# 08_-_RTD.net
KiCad netlist of a schematic drawn in Altium Designer
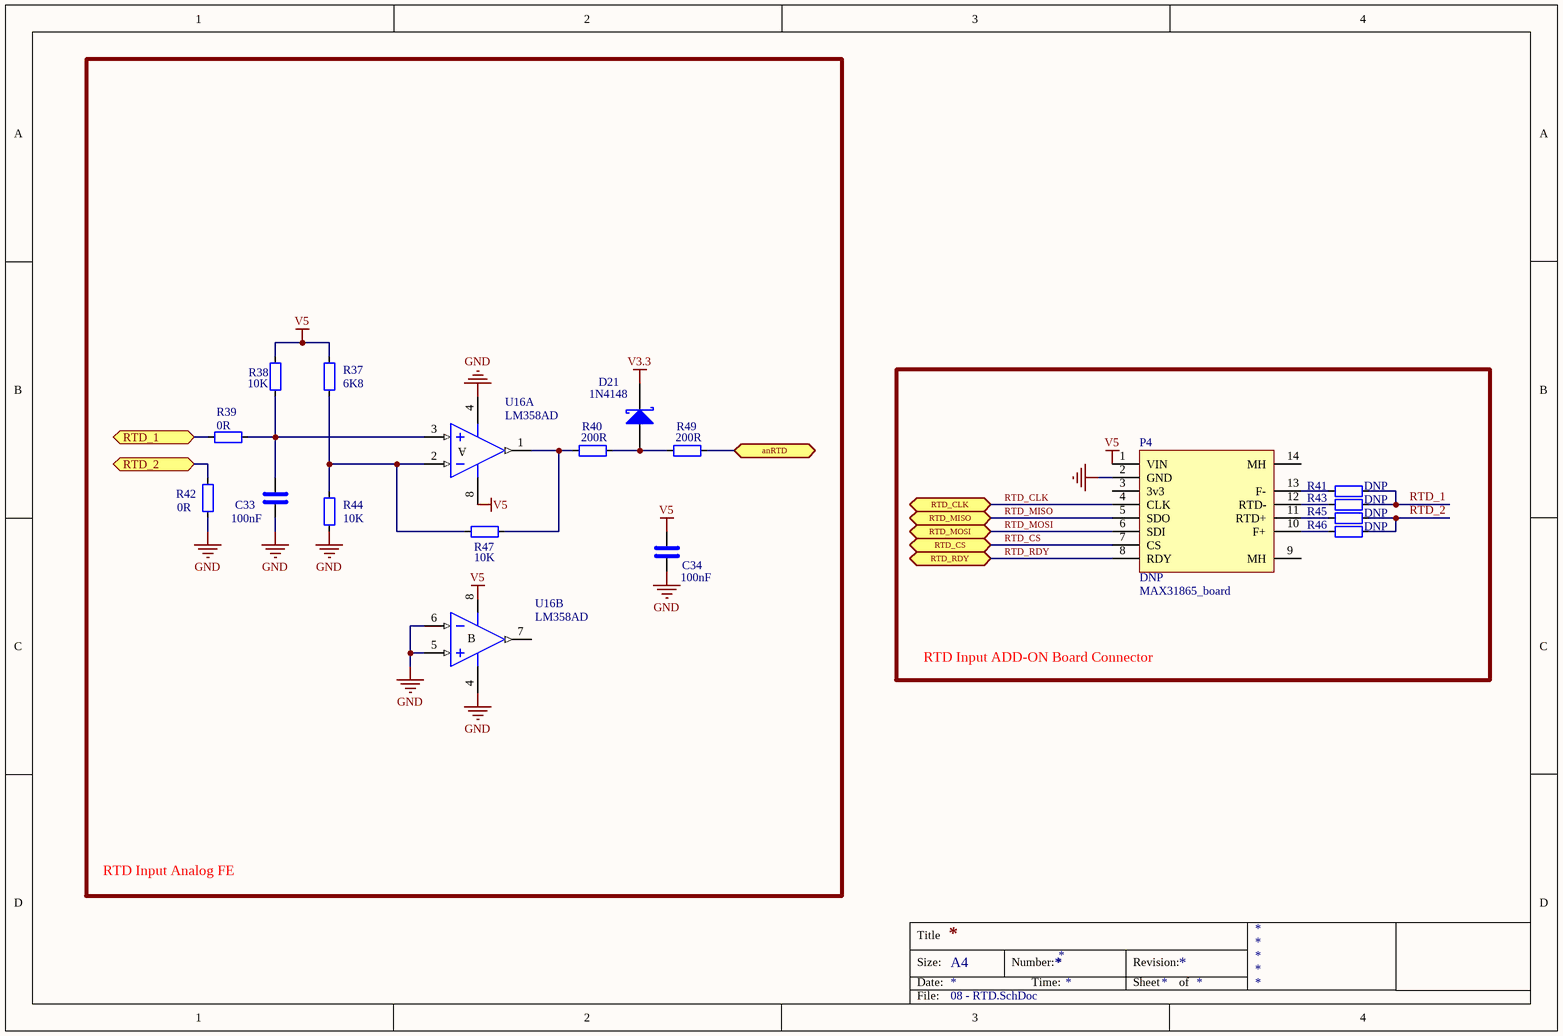
[diagram p0: 08 - RTD.SchDoc]

(export (version "E")
  (design (tool "Eeschema 10.0.6"))
  (components
    (comp (ref "C33")
      (value "100nF")
      (footprint "CAP_0603")
      (fields (field (name "LCSC PART") "C6119867"))
      (libsource (lib "WalterFeels") (part "C"))
    )
    (comp (ref "C34")
      (value "100nF")
      (footprint "CAP_0603")
      (fields (field (name "LCSC PART") "C6119867"))
      (libsource (lib "WalterFeels") (part "C"))
    )
    (comp (ref "D21")
      (value "1N4148")
      (footprint "SOD323_STM_NW")
      (description "1N4148_KA")
      (fields (field (name "LCSC PART") "C84063"))
      (libsource (lib "ahmet") (part "1N4148_KA"))
    )
    (comp (ref "P4")
      (value "DNP")
      (footprint "MAX31865_board")
      (description "MAX31865_board")
      (fields (field (name "ALTIUM_VALUE") "MAX31865_board") (field (name "PUBLISHER") "Altium Limited"))
      (libsource (lib "ahmet") (part "MAX31865_board"))
    )
    (comp (ref "R37")
      (value "6K8")
      (footprint "RES_0603")
      (fields (field (name "Comment") "60.4Ω"))
      (libsource (lib "") (part "R_1"))
    )
    (comp (ref "R38")
      (value "10K")
      (footprint "RES_0603")
      (fields (field (name "LCSC PART") "C25804") (field (name "Comment") "10K 1%"))
      (libsource (lib "Device") (part "R"))
    )
    (comp (ref "R39")
      (value "0R")
      (footprint "RES_0603")
      (fields (field (name "LCSC PART") "C15402"))
      (libsource (lib "") (part "R_2"))
    )
    (comp (ref "R40")
      (value "200R")
      (footprint "RES_0603")
      (fields (field (name "LCSC PART") "C2907123") (field (name "Comment") "200R %5"))
      (libsource (lib "") (part "R_2"))
    )
    (comp (ref "R41") (value "DNP") (footprint "RES_0603") (libsource (lib "") (part "R_3")))
    (comp (ref "R42")
      (value "0R")
      (footprint "RES_0603")
      (fields (field (name "LCSC PART") "C15402"))
      (libsource (lib "") (part "R_1"))
    )
    (comp (ref "R43") (value "DNP") (footprint "RES_0603") (libsource (lib "") (part "R_3")))
    (comp (ref "R44")
      (value "10K")
      (footprint "RES_0603")
      (fields (field (name "LCSC PART") "C25804") (field (name "Comment") "10K 1%"))
      (libsource (lib "Device") (part "R"))
    )
    (comp (ref "R45") (value "DNP") (footprint "RES_0603") (libsource (lib "") (part "R_3")))
    (comp (ref "R46") (value "DNP") (footprint "RES_0603") (libsource (lib "") (part "R_3")))
    (comp (ref "R47")
      (value "10K")
      (footprint "RES_0603")
      (fields (field (name "LCSC PART") "C25804") (field (name "Comment") "10K 1%"))
      (libsource (lib "") (part "R_3"))
    )
    (comp (ref "R49")
      (value "200R")
      (footprint "RES_0603")
      (fields (field (name "LCSC PART") "C2907123") (field (name "Comment") "200R %5"))
      (libsource (lib "") (part "R_2"))
    )
    (comp (ref "U16")
      (value "LM358AD")
      (footprint "SO8_M")
      (description "Low-Power Dual Operational Amplifier")
      (fields (field (name "LCSC PART") "C5423") (field (name "PUBLISHER") "Altium Limited"))
      (libsource (lib "ST Operational Amplifier") (part "LM358AD"))
    )
  )
  (nets
    (net (code "1") (name "/RTD_1") (class "Default")
      (node (ref "R39") (pin "1") (pinfunction "1_1") (pintype "passive"))
      (node (ref "R41") (pin "1") (pinfunction "1_1") (pintype "passive"))
      (node (ref "R43") (pin "1") (pinfunction "1_1") (pintype "passive"))
    )
    (net (code "2") (name "/RTD_2") (class "Default")
      (node (ref "R42") (pin "1") (pinfunction "1_1") (pintype "passive"))
      (node (ref "R45") (pin "1") (pinfunction "1_1") (pintype "passive"))
      (node (ref "R46") (pin "1") (pinfunction "1_1") (pintype "passive"))
    )
    (net (code "3") (name "/RTD_CLK") (class "Default")
      (node (ref "P4") (pin "4") (pinfunction "CLK_4") (pintype "passive"))
    )
    (net (code "4") (name "/RTD_CS") (class "Default")
      (node (ref "P4") (pin "7") (pinfunction "CS_7") (pintype "passive"))
    )
    (net (code "5") (name "/RTD_MISO") (class "Default")
      (node (ref "P4") (pin "5") (pinfunction "SDO_5") (pintype "passive"))
    )
    (net (code "6") (name "/RTD_MOSI") (class "Default")
      (node (ref "P4") (pin "6") (pinfunction "SDI_6") (pintype "passive"))
    )
    (net (code "7") (name "/RTD_RDY") (class "Default")
      (node (ref "P4") (pin "8") (pinfunction "RDY_8") (pintype "passive"))
    )
    (net (code "8") (name "/anRTD") (class "Default")
      (node (ref "R49") (pin "2") (pinfunction "2_2") (pintype "passive"))
    )
    (net (code "9") (name "GND") (class "Default")
      (node (ref "C33") (pin "2") (pinfunction "2_2") (pintype "passive"))
      (node (ref "C34") (pin "2") (pinfunction "2_2") (pintype "passive"))
      (node (ref "P4") (pin "2") (pinfunction "GND_2") (pintype "passive"))
      (node (ref "R42") (pin "2") (pinfunction "2_2") (pintype "passive"))
      (node (ref "R44") (pin "1") (pinfunction "1_1") (pintype "passive"))
      (node (ref "U16") (pin "4") (pinfunction "V-_4") (pintype "power_in"))
      (node (ref "U16") (pin "5") (pinfunction "IN+_5") (pintype "input"))
      (node (ref "U16") (pin "6") (pinfunction "IN-_6") (pintype "input"))
    )
    (net (code "10") (name "Net-(D21-A)") (class "Default")
      (node (ref "D21") (pin "2") (pinfunction "A_2") (pintype "passive"))
      (node (ref "R40") (pin "2") (pinfunction "2_2") (pintype "passive"))
      (node (ref "R49") (pin "1") (pinfunction "1_1") (pintype "passive"))
    )
    (net (code "11") (name "Net-(P4-F+)") (class "Default")
      (node (ref "P4") (pin "10") (pinfunction "F+_10") (pintype "passive"))
      (node (ref "R46") (pin "2") (pinfunction "2_2") (pintype "passive"))
    )
    (net (code "12") (name "Net-(P4-F-)") (class "Default")
      (node (ref "P4") (pin "13") (pinfunction "F-_13") (pintype "passive"))
      (node (ref "R41") (pin "2") (pinfunction "2_2") (pintype "passive"))
    )
    (net (code "13") (name "Net-(P4-RTD+)") (class "Default")
      (node (ref "P4") (pin "11") (pinfunction "RTD+_11") (pintype "passive"))
      (node (ref "R45") (pin "2") (pinfunction "2_2") (pintype "passive"))
    )
    (net (code "14") (name "Net-(P4-RTD-)") (class "Default")
      (node (ref "P4") (pin "12") (pinfunction "RTD-_12") (pintype "passive"))
      (node (ref "R43") (pin "2") (pinfunction "2_2") (pintype "passive"))
    )
    (net (code "15") (name "Net-(U16A-IN+)") (class "Default")
      (node (ref "C33") (pin "1") (pinfunction "1_1") (pintype "passive"))
      (node (ref "R38") (pin "1") (pinfunction "1_1") (pintype "passive"))
      (node (ref "R39") (pin "2") (pinfunction "2_2") (pintype "passive"))
      (node (ref "U16") (pin "3") (pinfunction "IN+_3") (pintype "input"))
    )
    (net (code "16") (name "Net-(U16A-IN-)") (class "Default")
      (node (ref "R37") (pin "2") (pinfunction "2_2") (pintype "passive"))
      (node (ref "R44") (pin "2") (pinfunction "2_2") (pintype "passive"))
      (node (ref "R47") (pin "2") (pinfunction "2_2") (pintype "passive"))
      (node (ref "U16") (pin "2") (pinfunction "IN-_2") (pintype "input"))
    )
    (net (code "17") (name "Net-(U16A-OUT)") (class "Default")
      (node (ref "R40") (pin "1") (pinfunction "1_1") (pintype "passive"))
      (node (ref "R47") (pin "1") (pinfunction "1_1") (pintype "passive"))
      (node (ref "U16") (pin "1") (pinfunction "OUT_1") (pintype "output"))
    )
    (net (code "18") (name "V3.3") (class "Default")
      (node (ref "D21") (pin "1") (pinfunction "K_1") (pintype "passive"))
    )
    (net (code "19") (name "V5") (class "Default")
      (node (ref "C34") (pin "1") (pinfunction "1_1") (pintype "passive"))
      (node (ref "P4") (pin "1") (pinfunction "VIN_1") (pintype "passive"))
      (node (ref "R37") (pin "1") (pinfunction "1_1") (pintype "passive"))
      (node (ref "R38") (pin "2") (pinfunction "2_2") (pintype "passive"))
      (node (ref "U16") (pin "8") (pinfunction "V+_8") (pintype "power_in"))
    )
    (net (code "20") (name "unconnected-(P4-3v3-Pad3)") (class "Default")
      (node (ref "P4") (pin "3") (pinfunction "3v3_3") (pintype "passive"))
    )
    (net (code "21") (name "unconnected-(P4-MH-Pad9)") (class "Default")
      (node (ref "P4") (pin "9") (pinfunction "MH_9") (pintype "passive"))
    )
    (net (code "22") (name "unconnected-(P4-MH-Pad14)") (class "Default")
      (node (ref "P4") (pin "14") (pinfunction "MH_14") (pintype "passive"))
    )
    (net (code "23") (name "unconnected-(U16B-OUT-Pad7)") (class "Default")
      (node (ref "U16") (pin "7") (pinfunction "OUT_7") (pintype "output"))
    )
    (net (code "24") (name "unconnected-(U16B-V+-Pad8)") (class "Default")
      (node (ref "U16") (pin "8") (pinfunction "V+_8") (pintype "power_in"))
    )
  )
)
